# IR.net
KiCad netlist of a schematic drawn in Altium Designer
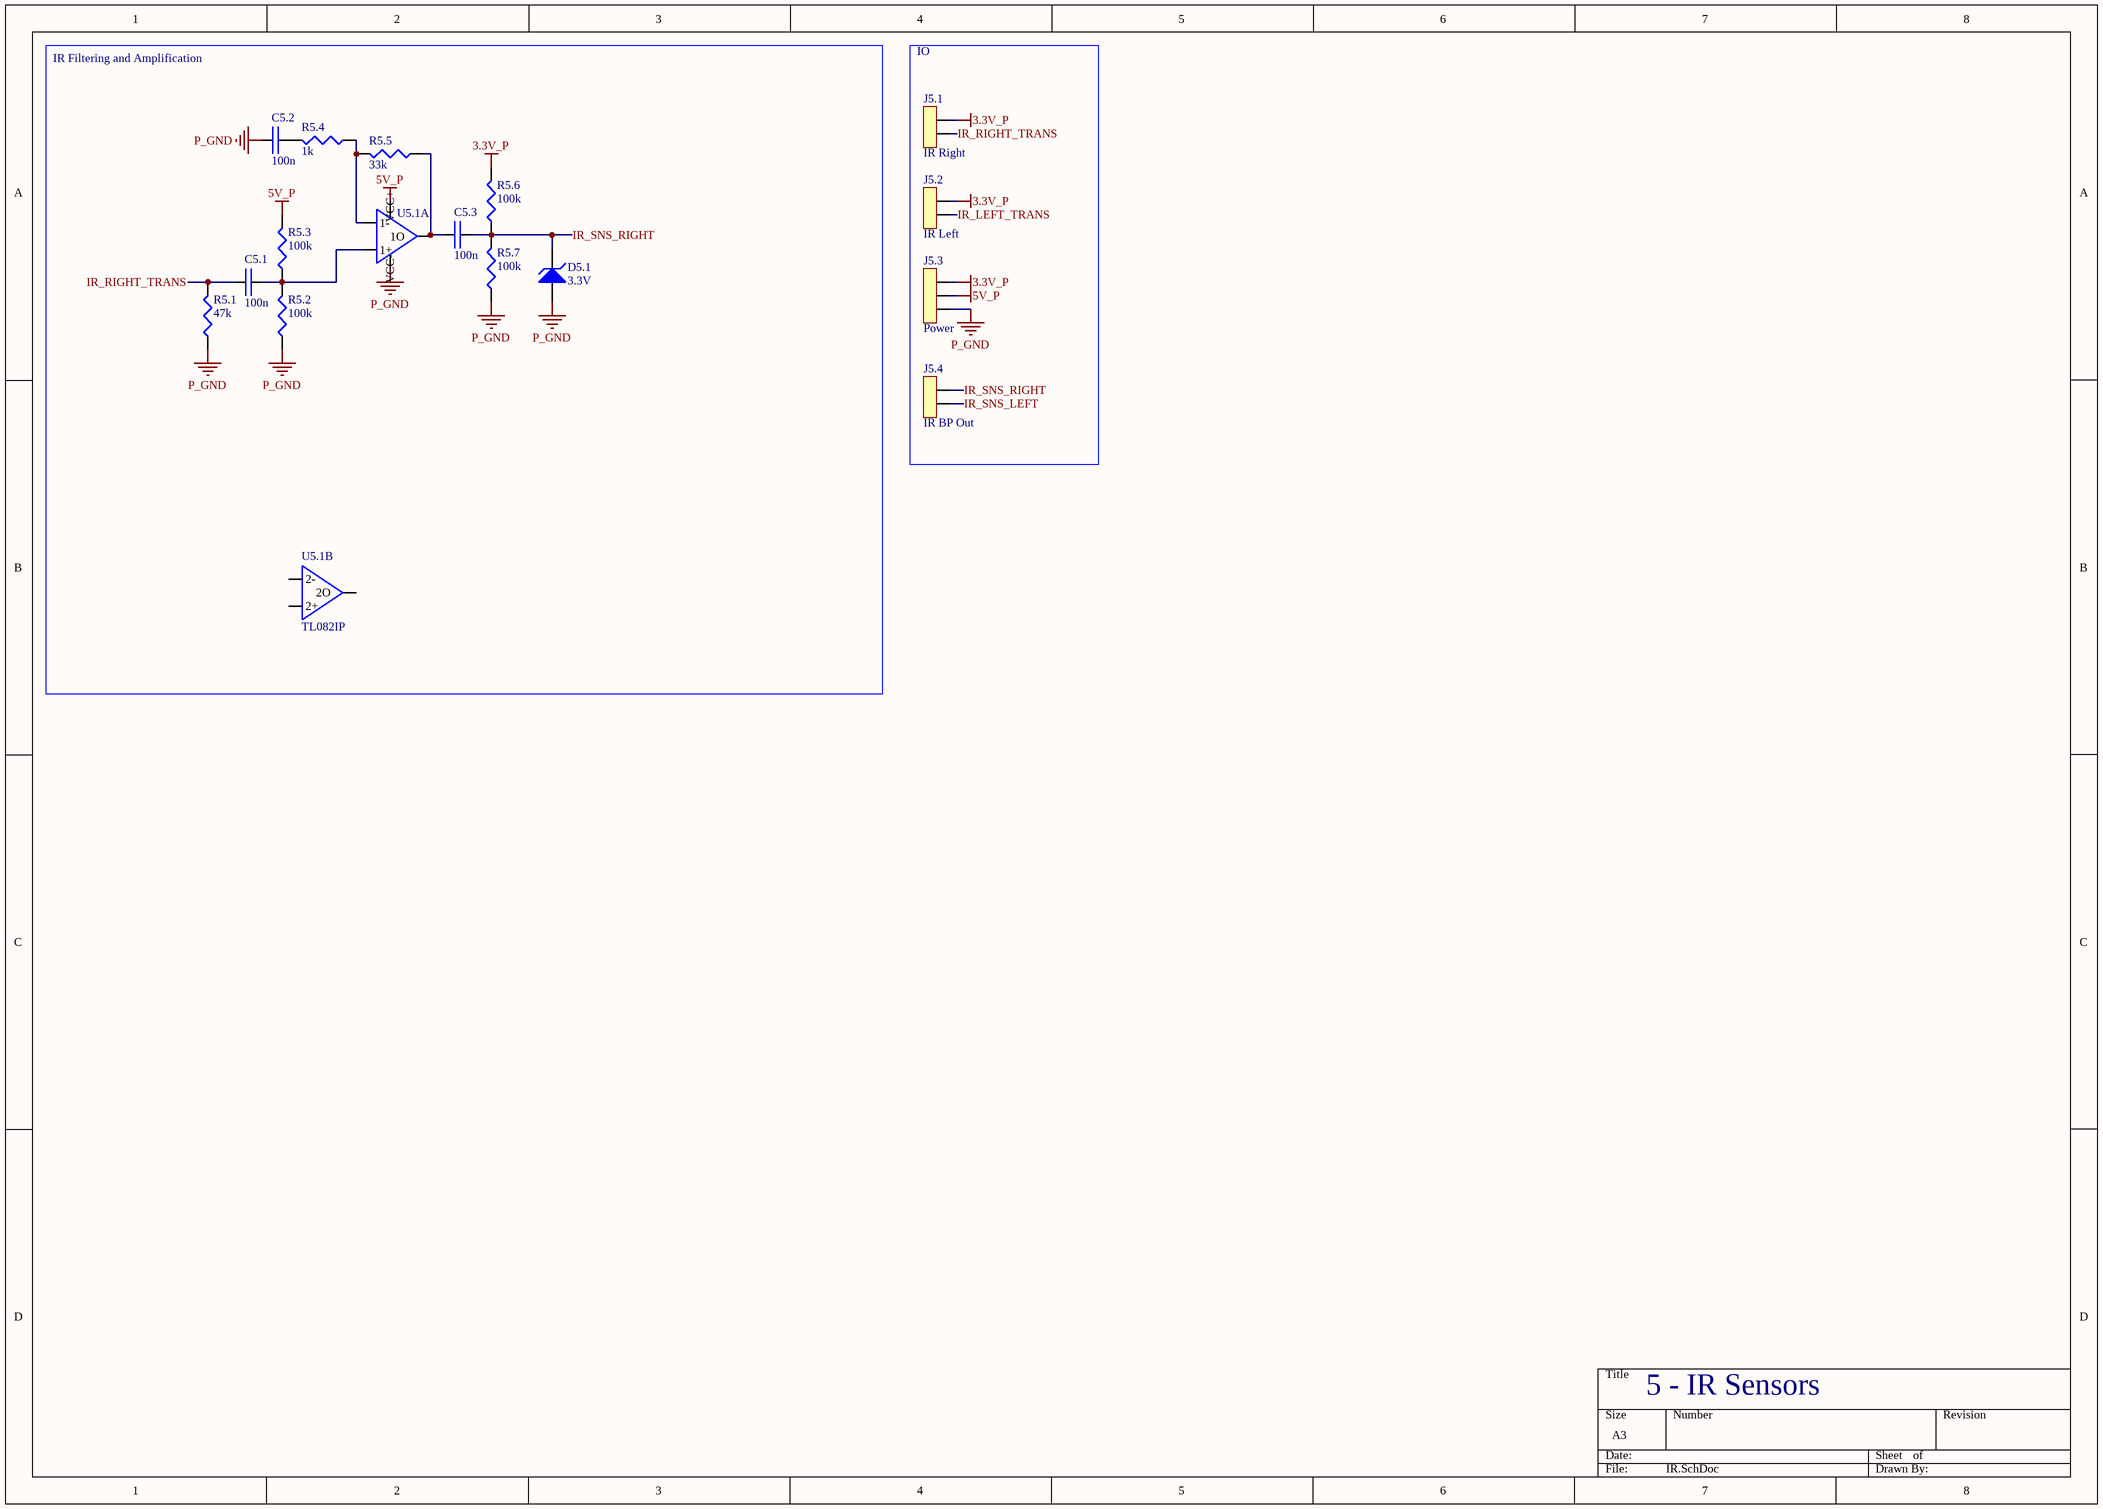
[diagram p0: IR.SchDoc]

(export (version "E")
  (design (tool "Eeschema 10.0.6"))
  (components
    (comp (ref "C5.1")
      (value "100n")
      (footprint "Non Polarized Cap")
      (libsource (lib "SPICEBot_SchLib") (part "Cap_Generic"))
    )
    (comp (ref "C5.2")
      (value "100n")
      (footprint "Non Polarized Cap")
      (libsource (lib "SPICEBot_SchLib") (part "Cap_Generic"))
    )
    (comp (ref "C5.3")
      (value "100n")
      (footprint "Non Polarized Cap")
      (libsource (lib "SPICEBot_SchLib") (part "Cap_Generic"))
    )
    (comp (ref "D5.1")
      (value "3.3V")
      (footprint "Zener Generic")
      (libsource (lib "SPICEBot_SchLib") (part "Zener_Generic"))
    )
    (comp (ref "J5.1")
      (value "IR Right")
      (footprint "2pos JST")
      (description "2pos Conn JST")
      (libsource (lib "SPICEBot_SchLib") (part "2pos Conn"))
    )
    (comp (ref "J5.2")
      (value "IR Left")
      (footprint "2pos JST")
      (description "2pos Conn JST")
      (libsource (lib "SPICEBot_SchLib") (part "2pos Conn"))
    )
    (comp (ref "J5.3")
      (value "Power")
      (footprint "3pos JST")
      (description "3pos Conn")
      (libsource (lib "SPICEBot_SchLib") (part "3pos Conn"))
    )
    (comp (ref "J5.4")
      (value "IR BP Out")
      (footprint "2pos JST")
      (description "2pos Conn JST")
      (libsource (lib "SPICEBot_SchLib") (part "2pos Conn"))
    )
    (comp (ref "R5.1")
      (value "47k")
      (footprint "Res_Generic")
      (libsource (lib "SPICEBot_SchLib") (part "Res_Generic"))
    )
    (comp (ref "R5.2")
      (value "100k")
      (footprint "Res_Generic")
      (libsource (lib "SPICEBot_SchLib") (part "Res_Generic"))
    )
    (comp (ref "R5.3")
      (value "100k")
      (footprint "Res_Generic")
      (libsource (lib "SPICEBot_SchLib") (part "Res_Generic"))
    )
    (comp (ref "R5.4")
      (value "1k")
      (footprint "Res_Generic")
      (libsource (lib "SPICEBot_SchLib") (part "Res_Generic"))
    )
    (comp (ref "R5.5")
      (value "33k")
      (footprint "Res_Generic")
      (libsource (lib "SPICEBot_SchLib") (part "Res_Generic"))
    )
    (comp (ref "R5.6")
      (value "100k")
      (footprint "Res_Generic")
      (libsource (lib "SPICEBot_SchLib") (part "Res_Generic"))
    )
    (comp (ref "R5.7")
      (value "100k")
      (footprint "Res_Generic")
      (libsource (lib "SPICEBot_SchLib") (part "Res_Generic"))
    )
    (comp (ref "U5.1")
      (value "TL082IP")
      (footprint "DIP8")
      (description "TL082IP IC OPAMP JFET 2 CIRCUIT 8DIP")
      (libsource (lib "SPICEBot_SchLib") (part "TL082IP Op Amp"))
    )
  )
  (nets
    (net (code "1") (name "/IR_LEFT_TRANS") (class "Default")
      (node (ref "J5.2") (pin "1") (pinfunction "1_1") (pintype "passive"))
    )
    (net (code "2") (name "/IR_RIGHT_TRANS") (class "Default")
      (node (ref "C5.1") (pin "1") (pinfunction "1_1") (pintype "passive"))
      (node (ref "J5.1") (pin "1") (pinfunction "1_1") (pintype "passive"))
      (node (ref "R5.1") (pin "2") (pinfunction "2_2") (pintype "passive"))
    )
    (net (code "3") (name "/IR_SNS_LEFT") (class "Default")
      (node (ref "J5.4") (pin "1") (pinfunction "1_1") (pintype "passive"))
    )
    (net (code "4") (name "/IR_SNS_RIGHT") (class "Default")
      (node (ref "C5.3") (pin "2") (pinfunction "2_2") (pintype "passive"))
      (node (ref "D5.1") (pin "2") (pinfunction "Cathode_2") (pintype "passive"))
      (node (ref "J5.4") (pin "2") (pinfunction "2_2") (pintype "passive"))
      (node (ref "R5.6") (pin "1") (pinfunction "1_1") (pintype "passive"))
      (node (ref "R5.7") (pin "2") (pinfunction "2_2") (pintype "passive"))
    )
    (net (code "5") (name "3.3V_P") (class "Default")
      (node (ref "J5.1") (pin "2") (pinfunction "2_2") (pintype "passive"))
      (node (ref "J5.2") (pin "2") (pinfunction "2_2") (pintype "passive"))
      (node (ref "J5.3") (pin "3") (pinfunction "3_3") (pintype "passive"))
      (node (ref "R5.6") (pin "2") (pinfunction "2_2") (pintype "passive"))
    )
    (net (code "6") (name "5V_P") (class "Default")
      (node (ref "J5.3") (pin "2") (pinfunction "2_2") (pintype "passive"))
      (node (ref "R5.3") (pin "2") (pinfunction "2_2") (pintype "passive"))
      (node (ref "U5.1") (pin "8") (pinfunction "VCC+_8") (pintype "passive"))
    )
    (net (code "7") (name "Net-(C5.2-Pad2)") (class "Default")
      (node (ref "C5.2") (pin "2") (pinfunction "2_2") (pintype "passive"))
      (node (ref "R5.4") (pin "2") (pinfunction "2_2") (pintype "passive"))
    )
    (net (code "8") (name "Net-(U5.1A-1+)") (class "Default")
      (node (ref "C5.1") (pin "2") (pinfunction "2_2") (pintype "passive"))
      (node (ref "R5.2") (pin "2") (pinfunction "2_2") (pintype "passive"))
      (node (ref "R5.3") (pin "1") (pinfunction "1_1") (pintype "passive"))
      (node (ref "U5.1") (pin "3") (pinfunction "1+_3") (pintype "passive"))
    )
    (net (code "9") (name "Net-(U5.1A-1-)") (class "Default")
      (node (ref "R5.4") (pin "1") (pinfunction "1_1") (pintype "passive"))
      (node (ref "R5.5") (pin "2") (pinfunction "2_2") (pintype "passive"))
      (node (ref "U5.1") (pin "2") (pinfunction "1-_2") (pintype "passive"))
    )
    (net (code "10") (name "Net-(U5.1A-1O)") (class "Default")
      (node (ref "C5.3") (pin "1") (pinfunction "1_1") (pintype "passive"))
      (node (ref "R5.5") (pin "1") (pinfunction "1_1") (pintype "passive"))
      (node (ref "U5.1") (pin "1") (pinfunction "1O_1") (pintype "passive"))
    )
    (net (code "11") (name "P_GND") (class "Default")
      (node (ref "C5.2") (pin "1") (pinfunction "1_1") (pintype "passive"))
      (node (ref "D5.1") (pin "1") (pinfunction "Anode_1") (pintype "passive"))
      (node (ref "J5.3") (pin "1") (pinfunction "1_1") (pintype "passive"))
      (node (ref "R5.1") (pin "1") (pinfunction "1_1") (pintype "passive"))
      (node (ref "R5.2") (pin "1") (pinfunction "1_1") (pintype "passive"))
      (node (ref "R5.7") (pin "1") (pinfunction "1_1") (pintype "passive"))
      (node (ref "U5.1") (pin "4") (pinfunction "VCC-_4") (pintype "passive"))
    )
    (net (code "12") (name "unconnected-(U5.1B-2+-Pad5)") (class "Default")
      (node (ref "U5.1") (pin "5") (pinfunction "2+_5") (pintype "passive"))
    )
    (net (code "13") (name "unconnected-(U5.1B-2--Pad6)") (class "Default")
      (node (ref "U5.1") (pin "6") (pinfunction "2-_6") (pintype "passive"))
    )
    (net (code "14") (name "unconnected-(U5.1B-2O-Pad7)") (class "Default")
      (node (ref "U5.1") (pin "7") (pinfunction "2O_7") (pintype "passive"))
    )
  )
)
